# cnc_lcd_buttons_sch.net
KiCad netlist of a schematic drawn in EAGLE
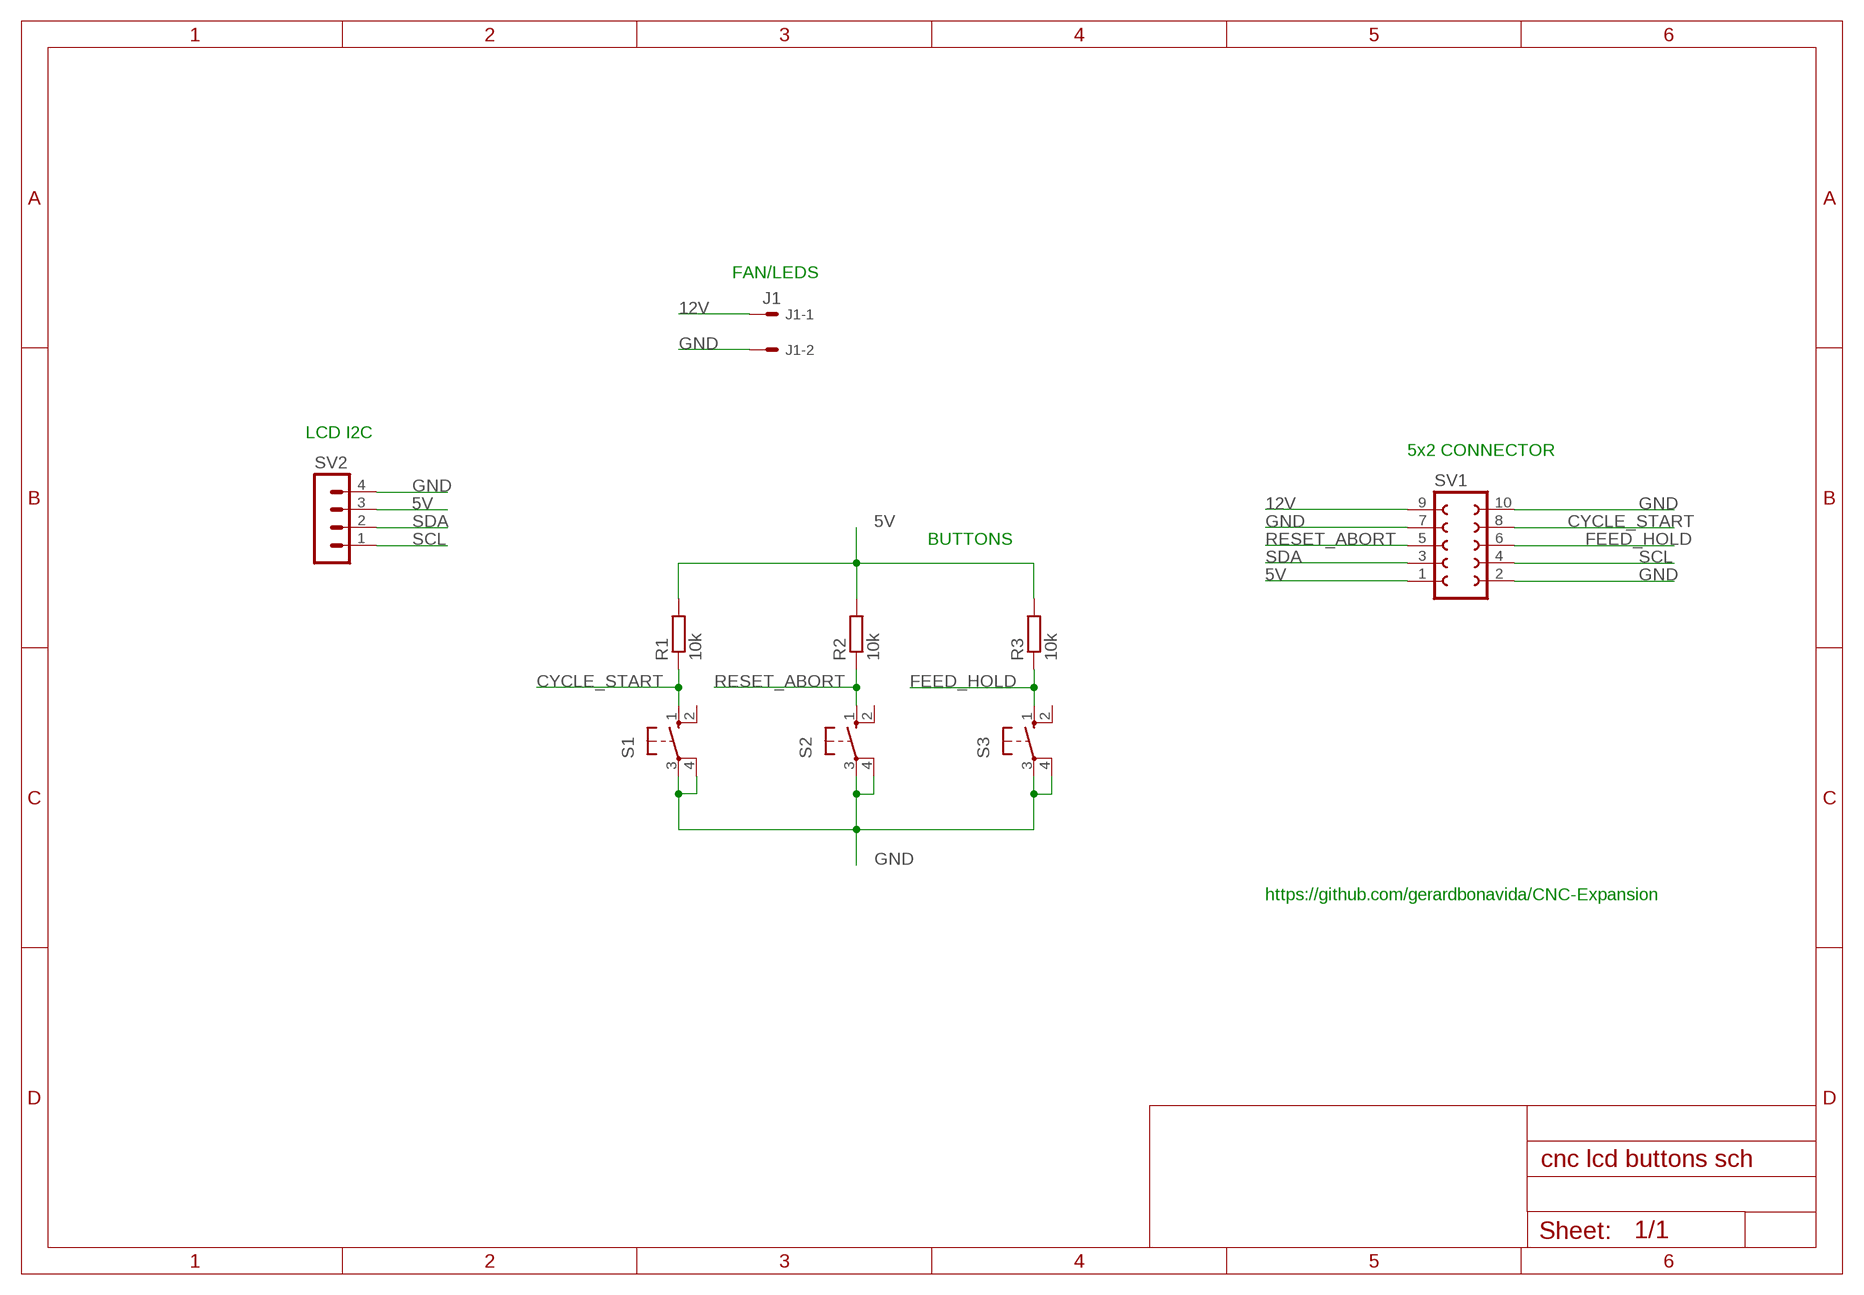
[diagram p0: schematic, sheet 1]

(export (version "E")
  (design (tool "Eeschema 10.0.6"))
  (components
    (comp (ref "J1")
      (value "J1")
      (footprint "eagle-import:6410-02")
      (libsource (lib "eagle-import") (part "22-?-0227-2021"))
    )
    (comp (ref "R1")
      (value "10k")
      (footprint "eagle-import:0309_12")
      (libsource (lib "eagle-import") (part "R-EU_0309/12"))
    )
    (comp (ref "R2")
      (value "10k")
      (footprint "eagle-import:0309_12")
      (libsource (lib "eagle-import") (part "R-EU_0309/12"))
    )
    (comp (ref "R3")
      (value "10k")
      (footprint "eagle-import:0309_12")
      (libsource (lib "eagle-import") (part "R-EU_0309/12"))
    )
    (comp (ref "S1")
      (value "10-XX")
      (footprint "eagle-import:B3F-10XX")
      (fields (field (name "MPN") "B3F-1000"))
      (libsource (lib "eagle-import") (part "10-XX"))
    )
    (comp (ref "S2")
      (value "10-XX")
      (footprint "eagle-import:B3F-10XX")
      (fields (field (name "MPN") "B3F-1000"))
      (libsource (lib "eagle-import") (part "10-XX"))
    )
    (comp (ref "S3")
      (value "10-XX")
      (footprint "eagle-import:B3F-10XX")
      (fields (field (name "MPN") "B3F-1000"))
      (libsource (lib "eagle-import") (part "10-XX"))
    )
    (comp (ref "SV1")
      (value "FE05-2")
      (footprint "eagle-import:FE05-2")
      (libsource (lib "eagle-import") (part "FE05-2"))
    )
    (comp (ref "SV2")
      (value "MA04-1")
      (footprint "eagle-import:MA04-1")
      (libsource (lib "eagle-import") (part "MA04-1"))
    )
  )
  (nets
    (net (code "1") (name "/5V") (class "Default")
      (node (ref "R1") (pin "2") (pinfunction "2_2") (pintype "passive"))
      (node (ref "R2") (pin "2") (pinfunction "2_2") (pintype "passive"))
      (node (ref "R3") (pin "2") (pinfunction "2_2") (pintype "passive"))
      (node (ref "SV1") (pin "1") (pinfunction "1_1") (pintype "passive"))
      (node (ref "SV2") (pin "3") (pinfunction "3_3") (pintype "passive"))
    )
    (net (code "2") (name "/12V") (class "Default")
      (node (ref "J1") (pin "1") (pinfunction "S_1") (pintype "passive"))
      (node (ref "SV1") (pin "9") (pinfunction "9_9") (pintype "passive"))
    )
    (net (code "3") (name "/CYCLE_START") (class "Default")
      (node (ref "R1") (pin "1") (pinfunction "1_1") (pintype "passive"))
      (node (ref "S1") (pin "1") (pinfunction "S_1") (pintype "passive"))
      (node (ref "SV1") (pin "8") (pinfunction "8_8") (pintype "passive"))
    )
    (net (code "4") (name "/FEED_HOLD") (class "Default")
      (node (ref "R3") (pin "1") (pinfunction "1_1") (pintype "passive"))
      (node (ref "S3") (pin "1") (pinfunction "S_1") (pintype "passive"))
      (node (ref "SV1") (pin "6") (pinfunction "6_6") (pintype "passive"))
    )
    (net (code "5") (name "/GND") (class "Default")
      (node (ref "J1") (pin "2") (pinfunction "S_2") (pintype "passive"))
      (node (ref "S1") (pin "3") (pinfunction "P_3") (pintype "passive"))
      (node (ref "S1") (pin "4") (pinfunction "P1_4") (pintype "passive"))
      (node (ref "S2") (pin "3") (pinfunction "P_3") (pintype "passive"))
      (node (ref "S2") (pin "4") (pinfunction "P1_4") (pintype "passive"))
      (node (ref "S3") (pin "3") (pinfunction "P_3") (pintype "passive"))
      (node (ref "S3") (pin "4") (pinfunction "P1_4") (pintype "passive"))
      (node (ref "SV1") (pin "10") (pinfunction "10_10") (pintype "passive"))
      (node (ref "SV1") (pin "2") (pinfunction "2_2") (pintype "passive"))
      (node (ref "SV1") (pin "7") (pinfunction "7_7") (pintype "passive"))
      (node (ref "SV2") (pin "4") (pinfunction "4_4") (pintype "passive"))
    )
    (net (code "6") (name "/RESET_ABORT") (class "Default")
      (node (ref "R2") (pin "1") (pinfunction "1_1") (pintype "passive"))
      (node (ref "S2") (pin "1") (pinfunction "S_1") (pintype "passive"))
      (node (ref "SV1") (pin "5") (pinfunction "5_5") (pintype "passive"))
    )
    (net (code "7") (name "/SCL") (class "Default")
      (node (ref "SV1") (pin "4") (pinfunction "4_4") (pintype "passive"))
      (node (ref "SV2") (pin "1") (pinfunction "1_1") (pintype "passive"))
    )
    (net (code "8") (name "/SDA") (class "Default")
      (node (ref "SV1") (pin "3") (pinfunction "3_3") (pintype "passive"))
      (node (ref "SV2") (pin "2") (pinfunction "2_2") (pintype "passive"))
    )
    (net (code "9") (name "unconnected-(S1-S1-Pad2)") (class "Default")
      (node (ref "S1") (pin "2") (pinfunction "S1_2") (pintype "passive"))
    )
    (net (code "10") (name "unconnected-(S2-S1-Pad2)") (class "Default")
      (node (ref "S2") (pin "2") (pinfunction "S1_2") (pintype "passive"))
    )
    (net (code "11") (name "unconnected-(S3-S1-Pad2)") (class "Default")
      (node (ref "S3") (pin "2") (pinfunction "S1_2") (pintype "passive"))
    )
  )
)
